# cv10_dobes.net
KiCad netlist of a schematic drawn in EAGLE
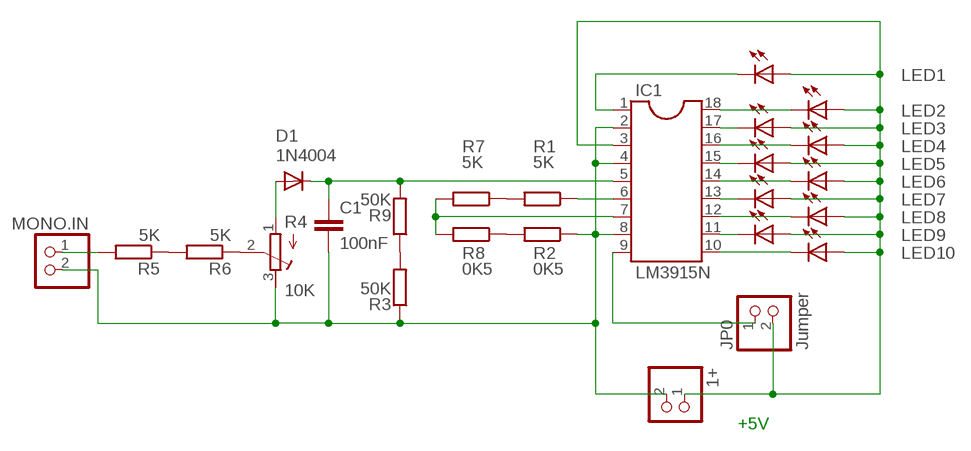
[diagram p0: schematic, sheet 1]

(export (version "E")
  (design (tool "Eeschema 10.0.6"))
  (components
    (comp (ref "1+")
      (value "PINHD-1X2")
      (footprint "eagle-import:1X02")
      (libsource (lib "eagle-import") (part "PINHD-1X2"))
    )
    (comp (ref "C1")
      (value "100nF")
      (footprint "eagle-import:C050-030X075")
      (libsource (lib "eagle-import") (part "C-EU050-030X075"))
    )
    (comp (ref "D1")
      (value "1N4004")
      (footprint "eagle-import:DO41-10")
      (libsource (lib "eagle-import") (part "1N4004"))
    )
    (comp (ref "IC1")
      (value "LM3915N")
      (footprint "eagle-import:SOCKET-18")
      (libsource (lib "eagle-import") (part "DIL18S"))
    )
    (comp (ref "JP0")
      (value "Jumper")
      (footprint "eagle-import:1X02")
      (libsource (lib "eagle-import") (part "PINHD-1X2"))
    )
    (comp (ref "LED1")
      (value "LED5MM")
      (footprint "eagle-import:LED5MM")
      (libsource (lib "eagle-import") (part "LED5MM"))
    )
    (comp (ref "LED2")
      (value "LED5MM")
      (footprint "eagle-import:LED5MM")
      (libsource (lib "eagle-import") (part "LED5MM"))
    )
    (comp (ref "LED3")
      (value "LED5MM")
      (footprint "eagle-import:LED5MM")
      (libsource (lib "eagle-import") (part "LED5MM"))
    )
    (comp (ref "LED4")
      (value "LED5MM")
      (footprint "eagle-import:LED5MM")
      (libsource (lib "eagle-import") (part "LED5MM"))
    )
    (comp (ref "LED5")
      (value "LED5MM")
      (footprint "eagle-import:LED5MM")
      (libsource (lib "eagle-import") (part "LED5MM"))
    )
    (comp (ref "LED6")
      (value "LED5MM")
      (footprint "eagle-import:LED5MM")
      (libsource (lib "eagle-import") (part "LED5MM"))
    )
    (comp (ref "LED7")
      (value "LED5MM")
      (footprint "eagle-import:LED5MM")
      (libsource (lib "eagle-import") (part "LED5MM"))
    )
    (comp (ref "LED8")
      (value "LED5MM")
      (footprint "eagle-import:LED5MM")
      (libsource (lib "eagle-import") (part "LED5MM"))
    )
    (comp (ref "LED9")
      (value "LED5MM")
      (footprint "eagle-import:LED5MM")
      (libsource (lib "eagle-import") (part "LED5MM"))
    )
    (comp (ref "LED10")
      (value "LED5MM")
      (footprint "eagle-import:LED5MM")
      (libsource (lib "eagle-import") (part "LED5MM"))
    )
    (comp (ref "MONO.IN")
      (value "PINHD-1X2")
      (footprint "eagle-import:1X02")
      (libsource (lib "eagle-import") (part "PINHD-1X2"))
    )
    (comp (ref "R1")
      (value "5K")
      (footprint "eagle-import:0207_7")
      (libsource (lib "eagle-import") (part "R-EU_0207/7"))
    )
    (comp (ref "R2")
      (value "0K5")
      (footprint "eagle-import:0207_7")
      (libsource (lib "eagle-import") (part "R-EU_0207/7"))
    )
    (comp (ref "R3")
      (value "50K")
      (footprint "eagle-import:0207_7")
      (libsource (lib "eagle-import") (part "R-EU_0207/7"))
    )
    (comp (ref "R4")
      (value "10K")
      (footprint "eagle-import:RTRIM64P")
      (libsource (lib "eagle-import") (part "R-TRIMM64P"))
    )
    (comp (ref "R5")
      (value "5K")
      (footprint "eagle-import:0207_7")
      (libsource (lib "eagle-import") (part "R-EU_0207/7"))
    )
    (comp (ref "R6")
      (value "5K")
      (footprint "eagle-import:0207_7")
      (libsource (lib "eagle-import") (part "R-EU_0207/7"))
    )
    (comp (ref "R7")
      (value "5K")
      (footprint "eagle-import:0207_7")
      (libsource (lib "eagle-import") (part "R-EU_0207/7"))
    )
    (comp (ref "R8")
      (value "0K5")
      (footprint "eagle-import:0207_7")
      (libsource (lib "eagle-import") (part "R-EU_0207/7"))
    )
    (comp (ref "R9")
      (value "50K")
      (footprint "eagle-import:0207_7")
      (libsource (lib "eagle-import") (part "R-EU_0207/7"))
    )
  )
  (nets
    (net (code "1") (name "Net-(1+-Pad1)") (class "Default")
      (node (ref "1+") (pin "1") (pinfunction "1_1") (pintype "passive"))
      (node (ref "IC1") (pin "3") (pinfunction "3_3") (pintype "passive"))
      (node (ref "JP0") (pin "2") (pinfunction "2_2") (pintype "passive"))
      (node (ref "LED1") (pin "A") (pinfunction "A_A") (pintype "passive"))
      (node (ref "LED10") (pin "A") (pinfunction "A_A") (pintype "passive"))
      (node (ref "LED2") (pin "A") (pinfunction "A_A") (pintype "passive"))
      (node (ref "LED3") (pin "A") (pinfunction "A_A") (pintype "passive"))
      (node (ref "LED4") (pin "A") (pinfunction "A_A") (pintype "passive"))
      (node (ref "LED5") (pin "A") (pinfunction "A_A") (pintype "passive"))
      (node (ref "LED6") (pin "A") (pinfunction "A_A") (pintype "passive"))
      (node (ref "LED7") (pin "A") (pinfunction "A_A") (pintype "passive"))
      (node (ref "LED8") (pin "A") (pinfunction "A_A") (pintype "passive"))
      (node (ref "LED9") (pin "A") (pinfunction "A_A") (pintype "passive"))
    )
    (net (code "2") (name "Net-(C1-Pad1)") (class "Default")
      (node (ref "C1") (pin "1") (pinfunction "1_1") (pintype "passive"))
      (node (ref "D1") (pin "C") (pinfunction "C_C") (pintype "passive"))
      (node (ref "IC1") (pin "5") (pinfunction "5_5") (pintype "passive"))
      (node (ref "R9") (pin "2") (pinfunction "2_2") (pintype "passive"))
    )
    (net (code "3") (name "Net-(IC1-Pad6)") (class "Default")
      (node (ref "IC1") (pin "6") (pinfunction "6_6") (pintype "passive"))
      (node (ref "R1") (pin "1") (pinfunction "1_1") (pintype "passive"))
    )
    (net (code "4") (name "Net-(IC1-Pad7)") (class "Default")
      (node (ref "IC1") (pin "7") (pinfunction "7_7") (pintype "passive"))
      (node (ref "R7") (pin "2") (pinfunction "2_2") (pintype "passive"))
      (node (ref "R8") (pin "2") (pinfunction "2_2") (pintype "passive"))
    )
    (net (code "5") (name "Net-(IC1-Pad9)") (class "Default")
      (node (ref "IC1") (pin "9") (pinfunction "9_9") (pintype "passive"))
      (node (ref "JP0") (pin "1") (pinfunction "1_1") (pintype "passive"))
    )
    (net (code "6") (name "Net-(LED1-C)") (class "Default")
      (node (ref "IC1") (pin "1") (pinfunction "1_1") (pintype "passive"))
      (node (ref "LED1") (pin "K") (pinfunction "C_K") (pintype "passive"))
    )
    (net (code "7") (name "Net-(LED2-C)") (class "Default")
      (node (ref "IC1") (pin "18") (pinfunction "18_18") (pintype "passive"))
      (node (ref "LED2") (pin "K") (pinfunction "C_K") (pintype "passive"))
    )
    (net (code "8") (name "Net-(LED3-C)") (class "Default")
      (node (ref "IC1") (pin "17") (pinfunction "17_17") (pintype "passive"))
      (node (ref "LED3") (pin "K") (pinfunction "C_K") (pintype "passive"))
    )
    (net (code "9") (name "Net-(LED4-C)") (class "Default")
      (node (ref "IC1") (pin "16") (pinfunction "16_16") (pintype "passive"))
      (node (ref "LED4") (pin "K") (pinfunction "C_K") (pintype "passive"))
    )
    (net (code "10") (name "Net-(LED5-C)") (class "Default")
      (node (ref "IC1") (pin "15") (pinfunction "15_15") (pintype "passive"))
      (node (ref "LED5") (pin "K") (pinfunction "C_K") (pintype "passive"))
    )
    (net (code "11") (name "Net-(LED6-C)") (class "Default")
      (node (ref "IC1") (pin "14") (pinfunction "14_14") (pintype "passive"))
      (node (ref "LED6") (pin "K") (pinfunction "C_K") (pintype "passive"))
    )
    (net (code "12") (name "Net-(LED7-C)") (class "Default")
      (node (ref "IC1") (pin "13") (pinfunction "13_13") (pintype "passive"))
      (node (ref "LED7") (pin "K") (pinfunction "C_K") (pintype "passive"))
    )
    (net (code "13") (name "Net-(LED8-C)") (class "Default")
      (node (ref "IC1") (pin "12") (pinfunction "12_12") (pintype "passive"))
      (node (ref "LED8") (pin "K") (pinfunction "C_K") (pintype "passive"))
    )
    (net (code "14") (name "Net-(LED9-C)") (class "Default")
      (node (ref "IC1") (pin "11") (pinfunction "11_11") (pintype "passive"))
      (node (ref "LED9") (pin "K") (pinfunction "C_K") (pintype "passive"))
    )
    (net (code "15") (name "Net-(LED10-C)") (class "Default")
      (node (ref "IC1") (pin "10") (pinfunction "10_10") (pintype "passive"))
      (node (ref "LED10") (pin "K") (pinfunction "C_K") (pintype "passive"))
    )
    (net (code "16") (name "Net-(MONO.IN-Pad1)") (class "Default")
      (node (ref "MONO.IN") (pin "1") (pinfunction "1_1") (pintype "passive"))
      (node (ref "R5") (pin "2") (pinfunction "2_2") (pintype "passive"))
    )
    (net (code "17") (name "Net-(R1-Pad2)") (class "Default")
      (node (ref "R1") (pin "2") (pinfunction "2_2") (pintype "passive"))
      (node (ref "R7") (pin "1") (pinfunction "1_1") (pintype "passive"))
    )
    (net (code "18") (name "Net-(R2-Pad2)") (class "Default")
      (node (ref "R2") (pin "2") (pinfunction "2_2") (pintype "passive"))
      (node (ref "R8") (pin "1") (pinfunction "1_1") (pintype "passive"))
    )
    (net (code "19") (name "Net-(R3-Pad2)") (class "Default")
      (node (ref "R3") (pin "2") (pinfunction "2_2") (pintype "passive"))
      (node (ref "R9") (pin "1") (pinfunction "1_1") (pintype "passive"))
    )
    (net (code "20") (name "Net-(R4-A)") (class "Default")
      (node (ref "1+") (pin "2") (pinfunction "2_2") (pintype "passive"))
      (node (ref "C1") (pin "2") (pinfunction "2_2") (pintype "passive"))
      (node (ref "IC1") (pin "2") (pinfunction "2_2") (pintype "passive"))
      (node (ref "IC1") (pin "4") (pinfunction "4_4") (pintype "passive"))
      (node (ref "IC1") (pin "8") (pinfunction "8_8") (pintype "passive"))
      (node (ref "MONO.IN") (pin "2") (pinfunction "2_2") (pintype "passive"))
      (node (ref "R2") (pin "1") (pinfunction "1_1") (pintype "passive"))
      (node (ref "R3") (pin "1") (pinfunction "1_1") (pintype "passive"))
      (node (ref "R4") (pin "3") (pinfunction "A_3") (pintype "passive"))
    )
    (net (code "21") (name "Net-(R4-E)") (class "Default")
      (node (ref "D1") (pin "A") (pinfunction "A_A") (pintype "passive"))
      (node (ref "R4") (pin "1") (pinfunction "E_1") (pintype "passive"))
    )
    (net (code "22") (name "Net-(R4-S)") (class "Default")
      (node (ref "R4") (pin "2") (pinfunction "S_2") (pintype "passive"))
      (node (ref "R6") (pin "1") (pinfunction "1_1") (pintype "passive"))
    )
    (net (code "23") (name "Net-(R5-Pad1)") (class "Default")
      (node (ref "R5") (pin "1") (pinfunction "1_1") (pintype "passive"))
      (node (ref "R6") (pin "2") (pinfunction "2_2") (pintype "passive"))
    )
  )
)
